# bqZUM_MCU.net
KiCad netlist of a schematic drawn in Altium Designer
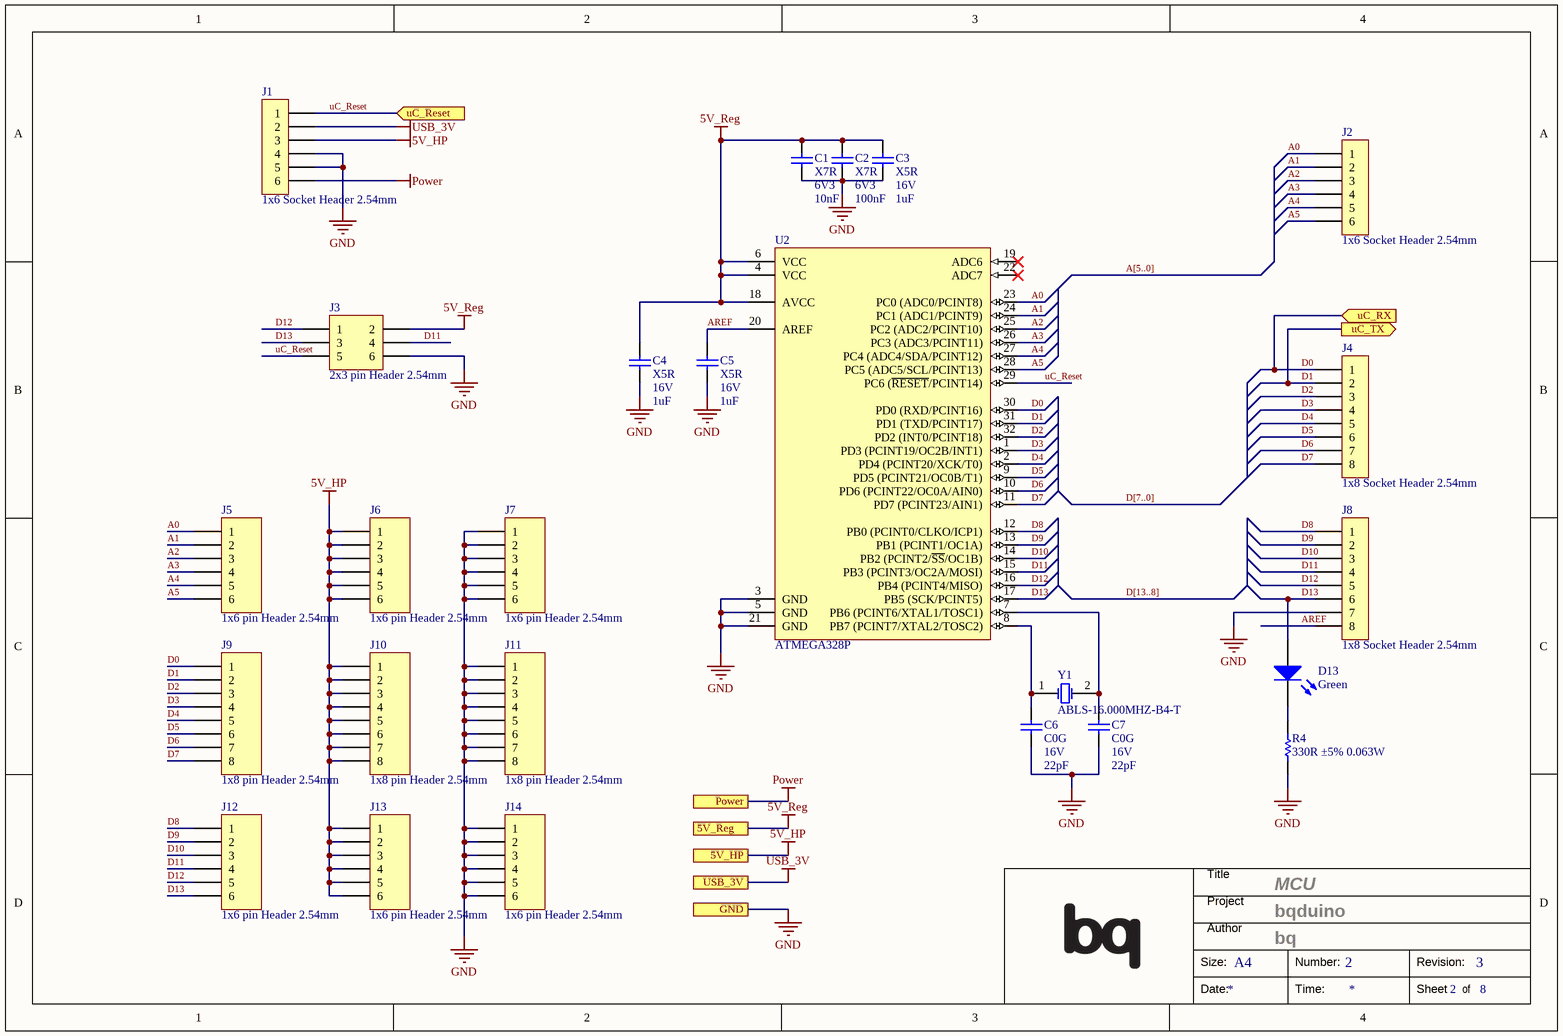
[diagram p0: bqZUM_MCU.SchDoc]

(export (version "E")
  (design (tool "Eeschema 10.0.6"))
  (components
    (comp (ref "C1")
      (value "Capacitor")
      (footprint "C0402")
      (fields
        (field (name "DIELECTRIC") "X7R")
        (field (name "VOLTAGE") "6V3")
        (field (name "CAPACITANCE") "10nF")
        (field (name "PART NUMBER") "C0402_10nF_6V3_±10%")
        (field (name "TOLERANCE") "±10%")
        (field (name "MANUFACTURER") "Kemet")
      )
      (libsource (lib "Pasives_Capacitor_SMD") (part "Capacitor"))
    )
    (comp (ref "C2")
      (value "Capacitor")
      (footprint "C0402")
      (fields
        (field (name "DIELECTRIC") "X7R")
        (field (name "VOLTAGE") "6V3")
        (field (name "CAPACITANCE") "100nF")
        (field (name "PART NUMBER") "C0402_100nF_6V3_±10%")
        (field (name "TOLERANCE") "±10%")
        (field (name "MANUFACTURER") "Kemet")
      )
      (libsource (lib "Pasives_Capacitor_SMD") (part "Capacitor"))
    )
    (comp (ref "C3")
      (value "Capacitor")
      (footprint "C0603")
      (fields
        (field (name "DIELECTRIC") "X5R")
        (field (name "VOLTAGE") "16V")
        (field (name "CAPACITANCE") "1uF")
        (field (name "PART NUMBER") "C0603_1uF_16V_±10%")
        (field (name "TOLERANCE") "±10%")
        (field (name "MANUFACTURER") "Kemet")
      )
      (libsource (lib "Pasives_Capacitor_SMD") (part "Capacitor"))
    )
    (comp (ref "C4")
      (value "Capacitor")
      (footprint "C0603")
      (fields
        (field (name "DIELECTRIC") "X5R")
        (field (name "VOLTAGE") "16V")
        (field (name "CAPACITANCE") "1uF")
        (field (name "PART NUMBER") "C0603_1uF_16V_±10%")
        (field (name "TOLERANCE") "±10%")
        (field (name "MANUFACTURER") "Kemet")
      )
      (libsource (lib "Pasives_Capacitor_SMD") (part "Capacitor"))
    )
    (comp (ref "C5")
      (value "Capacitor")
      (footprint "C0603")
      (fields
        (field (name "DIELECTRIC") "X5R")
        (field (name "VOLTAGE") "16V")
        (field (name "CAPACITANCE") "1uF")
        (field (name "PART NUMBER") "C0603_1uF_16V_±10%")
        (field (name "TOLERANCE") "±10%")
        (field (name "MANUFACTURER") "Kemet")
      )
      (libsource (lib "Pasives_Capacitor_SMD") (part "Capacitor"))
    )
    (comp (ref "C6")
      (value "Capacitor")
      (footprint "C0402")
      (fields
        (field (name "DIELECTRIC") "C0G")
        (field (name "VOLTAGE") "16V")
        (field (name "CAPACITANCE") "22pF")
        (field (name "PART NUMBER") "C0402_22pF_16V_±10%")
        (field (name "TOLERANCE") "±10%")
        (field (name "MANUFACTURER") "Kemet")
      )
      (libsource (lib "Pasives_Capacitor_SMD") (part "Capacitor"))
    )
    (comp (ref "C7")
      (value "Capacitor")
      (footprint "C0402")
      (fields
        (field (name "DIELECTRIC") "C0G")
        (field (name "VOLTAGE") "16V")
        (field (name "CAPACITANCE") "22pF")
        (field (name "PART NUMBER") "C0402_22pF_16V_±10%")
        (field (name "TOLERANCE") "±10%")
        (field (name "MANUFACTURER") "Kemet")
      )
      (libsource (lib "Pasives_Capacitor_SMD") (part "Capacitor"))
    )
    (comp (ref "D13")
      (value "Green")
      (footprint "LED0603")
      (description "Light Emitting Diode")
      (fields (field (name "PART NUMBER") "HSMG-C190") (field (name "MANUFACTURER") "Avago Technologies"))
      (libsource (lib "Optoelectronics") (part "LED"))
    )
    (comp (ref "J1")
      (value "1x6 Socket Header 2.54mm")
      (footprint "1x6 Socket Header THT 2.54mm")
      (description "6 pin Socket Header 2.54mm")
      (fields (field (name "MANUFACTURER") "Samtec") (field (name "PART NUMBER") "CON_SH_THT2.54_6"))
      (libsource (lib "") (part "1x6 Socket Header 2.54mm_1"))
    )
    (comp (ref "J2")
      (value "1x6 Socket Header 2.54mm")
      (footprint "1x6 Socket Header THT 2.54mm")
      (description "6 pin Socket Header 2.54mm")
      (fields (field (name "MANUFACTURER") "Samtec") (field (name "PART NUMBER") "CON_SH_THT2.54_6"))
      (libsource (lib "Conectores_SocketHeader_2.54") (part "1x6 Socket Header 2.54mm"))
    )
    (comp (ref "J3")
      (value "2x3 pin Header 2.54mm")
      (footprint "2x3 Pin Header 2.54")
      (description "6 pin Dual Header 2.54mm")
      (fields (field (name "MANUFACTURER") "Samtec") (field (name "PART NUMBER") "CON_DPH_THT2.54_6"))
      (libsource (lib "Conectores_PinHeader_2.54") (part "2x3 pin Header 2.54mm"))
    )
    (comp (ref "J4")
      (value "1x8 Socket Header 2.54mm")
      (footprint "1x8 Socket Header THT 2.54mm")
      (description "8 pin Socket Header 2.54mm")
      (fields (field (name "MANUFACTURER") "Samtec") (field (name "PART NUMBER") "CON_SH_THT2.54_8"))
      (libsource (lib "Conectores_SocketHeader_2.54") (part "1x8 Socket Header 2.54mm"))
    )
    (comp (ref "J5")
      (value "1x6 pin Header 2.54mm")
      (footprint "1x6 Pin Header 2.54")
      (fields (field (name "MANUFACTURER") "Samtec") (field (name "PART NUMBER") "CON_PH_THT2.54_6 Blue"))
      (libsource (lib "Conectores_PinHeader_2.54") (part "1x6 pin Header 2.54mm"))
    )
    (comp (ref "J6")
      (value "1x6 pin Header 2.54mm")
      (footprint "1x6 Pin Header 2.54")
      (fields (field (name "MANUFACTURER") "Samtec") (field (name "PART NUMBER") "CON_PH_THT2.54_6 Red"))
      (libsource (lib "Conectores_PinHeader_2.54") (part "1x6 pin Header 2.54mm"))
    )
    (comp (ref "J7")
      (value "1x6 pin Header 2.54mm")
      (footprint "1x6 Pin Header 2.54")
      (fields (field (name "MANUFACTURER") "Samtec") (field (name "PART NUMBER") "CON_PH_THT2.54_6"))
      (libsource (lib "Conectores_PinHeader_2.54") (part "1x6 pin Header 2.54mm"))
    )
    (comp (ref "J8")
      (value "1x8 Socket Header 2.54mm")
      (footprint "1x8 Socket Header THT 2.54mm")
      (description "8 pin Socket Header 2.54mm")
      (fields (field (name "MANUFACTURER") "Samtec") (field (name "PART NUMBER") "CON_SH_THT2.54_8"))
      (libsource (lib "Conectores_SocketHeader_2.54") (part "1x8 Socket Header 2.54mm"))
    )
    (comp (ref "J9")
      (value "1x8 pin Header 2.54mm")
      (footprint "1x8 Pin Header 2.54")
      (fields (field (name "MANUFACTURER") "Samtec") (field (name "PART NUMBER") "CON_PH_THT2.54_8 Natural"))
      (libsource (lib "Conectores_PinHeader_2.54") (part "1x8 pin Header 2.54mm"))
    )
    (comp (ref "J10")
      (value "1x8 pin Header 2.54mm")
      (footprint "1x8 Pin Header 2.54")
      (fields (field (name "MANUFACTURER") "Samtec") (field (name "PART NUMBER") "CON_PH_THT2.54_8 Red"))
      (libsource (lib "Conectores_PinHeader_2.54") (part "1x8 pin Header 2.54mm"))
    )
    (comp (ref "J11")
      (value "1x8 pin Header 2.54mm")
      (footprint "1x8 Pin Header 2.54")
      (fields (field (name "MANUFACTURER") "Samtec") (field (name "PART NUMBER") "CON_PH_THT2.54_8"))
      (libsource (lib "Conectores_PinHeader_2.54") (part "1x8 pin Header 2.54mm"))
    )
    (comp (ref "J12")
      (value "1x6 pin Header 2.54mm")
      (footprint "1x6 Pin Header 2.54")
      (fields (field (name "MANUFACTURER") "Samtec") (field (name "PART NUMBER") "CON_PH_THT2.54_6 Natural"))
      (libsource (lib "Conectores_PinHeader_2.54") (part "1x6 pin Header 2.54mm"))
    )
    (comp (ref "J13")
      (value "1x6 pin Header 2.54mm")
      (footprint "1x6 Pin Header 2.54")
      (fields (field (name "MANUFACTURER") "Samtec") (field (name "PART NUMBER") "CON_PH_THT2.54_6 Red"))
      (libsource (lib "Conectores_PinHeader_2.54") (part "1x6 pin Header 2.54mm"))
    )
    (comp (ref "J14")
      (value "1x6 pin Header 2.54mm")
      (footprint "1x6 Pin Header 2.54")
      (fields (field (name "MANUFACTURER") "Samtec") (field (name "PART NUMBER") "CON_PH_THT2.54_6"))
      (libsource (lib "Conectores_PinHeader_2.54") (part "1x6 pin Header 2.54mm"))
    )
    (comp (ref "R4")
      (value "330R ±5% 0.063W")
      (footprint "R0402")
      (description "Resistor")
      (fields (field (name "TOLERANCE") "±5%") (field (name "POWER") "0.063W"))
      (libsource (lib "Pasives_Resistor_SMD") (part "Resistor"))
    )
    (comp (ref "U2")
      (value "ATMEGA328P")
      (footprint "TQFP32")
      (description "8-bit AVR Microcontroller")
      (fields (field (name "MANUFACTURER") "Atmel"))
      (libsource (lib "Processor") (part "ATMEGA328P"))
    )
    (comp (ref "Y1")
      (value "ABLS-16.000MHZ-B4-T")
      (footprint "XTAL 11.4x4.7")
      (description "Crystal")
      (fields (field (name "PART NUMBER") "ABLS 16MHz") (field (name "TOLERANCE") "±30ppm"))
      (libsource (lib "Frequency") (part "Crystal 2 pin"))
    )
  )
  (nets
    (net (code "1") (name "/A0") (class "Default")
      (node (ref "J2") (pin "1") (pinfunction "1_1") (pintype "passive"))
      (node (ref "J5") (pin "1") (pinfunction "1_1") (pintype "passive"))
      (node (ref "U2") (pin "23") (pinfunction "PC0_(ADC0/PCINT8)_23") (pintype "bidirectional"))
    )
    (net (code "2") (name "/A1") (class "Default")
      (node (ref "J2") (pin "2") (pinfunction "2_2") (pintype "passive"))
      (node (ref "J5") (pin "2") (pinfunction "2_2") (pintype "passive"))
      (node (ref "U2") (pin "24") (pinfunction "PC1_(ADC1/PCINT9)_24") (pintype "bidirectional"))
    )
    (net (code "3") (name "/A2") (class "Default")
      (node (ref "J2") (pin "3") (pinfunction "3_3") (pintype "passive"))
      (node (ref "J5") (pin "3") (pinfunction "3_3") (pintype "passive"))
      (node (ref "U2") (pin "25") (pinfunction "PC2_(ADC2/PCINT10)_25") (pintype "bidirectional"))
    )
    (net (code "4") (name "/A3") (class "Default")
      (node (ref "J2") (pin "4") (pinfunction "4_4") (pintype "passive"))
      (node (ref "J5") (pin "4") (pinfunction "4_4") (pintype "passive"))
      (node (ref "U2") (pin "26") (pinfunction "PC3_(ADC3/PCINT11)_26") (pintype "bidirectional"))
    )
    (net (code "5") (name "/A4") (class "Default")
      (node (ref "J2") (pin "5") (pinfunction "5_5") (pintype "passive"))
      (node (ref "J5") (pin "5") (pinfunction "5_5") (pintype "passive"))
      (node (ref "U2") (pin "27") (pinfunction "PC4_(ADC4/SDA/PCINT12)_27") (pintype "bidirectional"))
    )
    (net (code "6") (name "/A5") (class "Default")
      (node (ref "J2") (pin "6") (pinfunction "6_6") (pintype "passive"))
      (node (ref "J5") (pin "6") (pinfunction "6_6") (pintype "passive"))
      (node (ref "U2") (pin "28") (pinfunction "PC5_(ADC5/SCL/PCINT13)_28") (pintype "bidirectional"))
    )
    (net (code "7") (name "/AREF") (class "Default")
      (node (ref "C5") (pin "2") (pinfunction "2_2") (pintype "passive"))
      (node (ref "J8") (pin "8") (pinfunction "8_8") (pintype "passive"))
      (node (ref "U2") (pin "20") (pinfunction "AREF_20") (pintype "passive"))
    )
    (net (code "9") (name "/D0") (class "Default")
      (node (ref "J4") (pin "1") (pinfunction "1_1") (pintype "passive"))
      (node (ref "J9") (pin "1") (pinfunction "1_1") (pintype "passive"))
      (node (ref "U2") (pin "30") (pinfunction "PD0_(RXD/PCINT16)_30") (pintype "bidirectional"))
    )
    (net (code "10") (name "/D1") (class "Default")
      (node (ref "J4") (pin "2") (pinfunction "2_2") (pintype "passive"))
      (node (ref "J9") (pin "2") (pinfunction "2_2") (pintype "passive"))
      (node (ref "U2") (pin "31") (pinfunction "PD1_(TXD/PCINT17)_31") (pintype "bidirectional"))
    )
    (net (code "11") (name "/D2") (class "Default")
      (node (ref "J4") (pin "3") (pinfunction "3_3") (pintype "passive"))
      (node (ref "J9") (pin "3") (pinfunction "3_3") (pintype "passive"))
      (node (ref "U2") (pin "32") (pinfunction "PD2_(INT0/PCINT18)_32") (pintype "bidirectional"))
    )
    (net (code "12") (name "/D3") (class "Default")
      (node (ref "J4") (pin "4") (pinfunction "4_4") (pintype "passive"))
      (node (ref "J9") (pin "4") (pinfunction "4_4") (pintype "passive"))
      (node (ref "U2") (pin "1") (pinfunction "PD3_(PCINT19/OC2B/INT1)_1") (pintype "bidirectional"))
    )
    (net (code "13") (name "/D4") (class "Default")
      (node (ref "J4") (pin "5") (pinfunction "5_5") (pintype "passive"))
      (node (ref "J9") (pin "5") (pinfunction "5_5") (pintype "passive"))
      (node (ref "U2") (pin "2") (pinfunction "PD4_(PCINT20/XCK/T0)_2") (pintype "bidirectional"))
    )
    (net (code "14") (name "/D5") (class "Default")
      (node (ref "J4") (pin "6") (pinfunction "6_6") (pintype "passive"))
      (node (ref "J9") (pin "6") (pinfunction "6_6") (pintype "passive"))
      (node (ref "U2") (pin "9") (pinfunction "PD5_(PCINT21/OC0B/T1)_9") (pintype "bidirectional"))
    )
    (net (code "15") (name "/D6") (class "Default")
      (node (ref "J4") (pin "7") (pinfunction "7_7") (pintype "passive"))
      (node (ref "J9") (pin "7") (pinfunction "7_7") (pintype "passive"))
      (node (ref "U2") (pin "10") (pinfunction "PD6_(PCINT22/OC0A/AIN0)_10") (pintype "bidirectional"))
    )
    (net (code "16") (name "/D7") (class "Default")
      (node (ref "J4") (pin "8") (pinfunction "8_8") (pintype "passive"))
      (node (ref "J9") (pin "8") (pinfunction "8_8") (pintype "passive"))
      (node (ref "U2") (pin "11") (pinfunction "PD7_(PCINT23/AIN1)_11") (pintype "bidirectional"))
    )
    (net (code "17") (name "/D8") (class "Default")
      (node (ref "J12") (pin "1") (pinfunction "1_1") (pintype "passive"))
      (node (ref "J8") (pin "1") (pinfunction "1_1") (pintype "passive"))
      (node (ref "U2") (pin "12") (pinfunction "PB0_(PCINT0/CLKO/ICP1)_12") (pintype "bidirectional"))
    )
    (net (code "18") (name "/D9") (class "Default")
      (node (ref "J12") (pin "2") (pinfunction "2_2") (pintype "passive"))
      (node (ref "J8") (pin "2") (pinfunction "2_2") (pintype "passive"))
      (node (ref "U2") (pin "13") (pinfunction "PB1_(PCINT1/OC1A)_13") (pintype "bidirectional"))
    )
    (net (code "19") (name "/D10") (class "Default")
      (node (ref "J12") (pin "3") (pinfunction "3_3") (pintype "passive"))
      (node (ref "J8") (pin "3") (pinfunction "3_3") (pintype "passive"))
      (node (ref "U2") (pin "14") (pinfunction "PB2_(PCINT2/~{SS}/OC1B)_14") (pintype "bidirectional"))
    )
    (net (code "20") (name "/D11") (class "Default")
      (node (ref "J12") (pin "4") (pinfunction "4_4") (pintype "passive"))
      (node (ref "J3") (pin "4") (pinfunction "4_4") (pintype "passive"))
      (node (ref "J8") (pin "4") (pinfunction "4_4") (pintype "passive"))
      (node (ref "U2") (pin "15") (pinfunction "PB3_(PCINT3/OC2A/MOSI)_15") (pintype "bidirectional"))
    )
    (net (code "21") (name "/D12") (class "Default")
      (node (ref "J12") (pin "5") (pinfunction "5_5") (pintype "passive"))
      (node (ref "J3") (pin "1") (pinfunction "1_1") (pintype "passive"))
      (node (ref "J8") (pin "5") (pinfunction "5_5") (pintype "passive"))
      (node (ref "U2") (pin "16") (pinfunction "PB4_(PCINT4/MISO)_16") (pintype "bidirectional"))
    )
    (net (code "22") (name "/D13") (class "Default")
      (node (ref "D13") (pin "A") (pinfunction "A_A") (pintype "passive"))
      (node (ref "J12") (pin "6") (pinfunction "6_6") (pintype "passive"))
      (node (ref "J3") (pin "3") (pinfunction "3_3") (pintype "passive"))
      (node (ref "J8") (pin "6") (pinfunction "6_6") (pintype "passive"))
      (node (ref "U2") (pin "17") (pinfunction "PB5_(SCK/PCINT5)_17") (pintype "bidirectional"))
    )
    (net (code "25") (name "/uC_Reset") (class "Default")
      (node (ref "J1") (pin "1") (pinfunction "1_1") (pintype "passive"))
      (node (ref "J3") (pin "5") (pinfunction "5_5") (pintype "passive"))
      (node (ref "U2") (pin "29") (pinfunction "PC6_(~{RESET}/PCINT14)_29") (pintype "bidirectional"))
    )
    (net (code "26") (name "5V_HP") (class "Default")
      (node (ref "J1") (pin "3") (pinfunction "3_3") (pintype "passive"))
      (node (ref "J10") (pin "1") (pinfunction "1_1") (pintype "passive"))
      (node (ref "J10") (pin "2") (pinfunction "2_2") (pintype "passive"))
      (node (ref "J10") (pin "3") (pinfunction "3_3") (pintype "passive"))
      (node (ref "J10") (pin "4") (pinfunction "4_4") (pintype "passive"))
      (node (ref "J10") (pin "5") (pinfunction "5_5") (pintype "passive"))
      (node (ref "J10") (pin "6") (pinfunction "6_6") (pintype "passive"))
      (node (ref "J10") (pin "7") (pinfunction "7_7") (pintype "passive"))
      (node (ref "J10") (pin "8") (pinfunction "8_8") (pintype "passive"))
      (node (ref "J13") (pin "1") (pinfunction "1_1") (pintype "passive"))
      (node (ref "J13") (pin "2") (pinfunction "2_2") (pintype "passive"))
      (node (ref "J13") (pin "3") (pinfunction "3_3") (pintype "passive"))
      (node (ref "J13") (pin "4") (pinfunction "4_4") (pintype "passive"))
      (node (ref "J13") (pin "5") (pinfunction "5_5") (pintype "passive"))
      (node (ref "J13") (pin "6") (pinfunction "6_6") (pintype "passive"))
      (node (ref "J6") (pin "1") (pinfunction "1_1") (pintype "passive"))
      (node (ref "J6") (pin "2") (pinfunction "2_2") (pintype "passive"))
      (node (ref "J6") (pin "3") (pinfunction "3_3") (pintype "passive"))
      (node (ref "J6") (pin "4") (pinfunction "4_4") (pintype "passive"))
      (node (ref "J6") (pin "5") (pinfunction "5_5") (pintype "passive"))
      (node (ref "J6") (pin "6") (pinfunction "6_6") (pintype "passive"))
    )
    (net (code "27") (name "5V_Reg") (class "Default")
      (node (ref "C1") (pin "2") (pinfunction "2_2") (pintype "passive"))
      (node (ref "C2") (pin "2") (pinfunction "2_2") (pintype "passive"))
      (node (ref "C3") (pin "2") (pinfunction "2_2") (pintype "passive"))
      (node (ref "C4") (pin "2") (pinfunction "2_2") (pintype "passive"))
      (node (ref "J3") (pin "2") (pinfunction "2_2") (pintype "passive"))
      (node (ref "U2") (pin "18") (pinfunction "AVCC_18") (pintype "power_in"))
      (node (ref "U2") (pin "4") (pinfunction "VCC_4") (pintype "power_in"))
      (node (ref "U2") (pin "6") (pinfunction "VCC_6") (pintype "power_in"))
    )
    (net (code "28") (name "GND") (class "Default")
      (node (ref "C1") (pin "1") (pinfunction "1_1") (pintype "passive"))
      (node (ref "C2") (pin "1") (pinfunction "1_1") (pintype "passive"))
      (node (ref "C3") (pin "1") (pinfunction "1_1") (pintype "passive"))
      (node (ref "C4") (pin "1") (pinfunction "1_1") (pintype "passive"))
      (node (ref "C5") (pin "1") (pinfunction "1_1") (pintype "passive"))
      (node (ref "C6") (pin "1") (pinfunction "1_1") (pintype "passive"))
      (node (ref "C7") (pin "1") (pinfunction "1_1") (pintype "passive"))
      (node (ref "J1") (pin "4") (pinfunction "4_4") (pintype "passive"))
      (node (ref "J1") (pin "5") (pinfunction "5_5") (pintype "passive"))
      (node (ref "J11") (pin "1") (pinfunction "1_1") (pintype "passive"))
      (node (ref "J11") (pin "2") (pinfunction "2_2") (pintype "passive"))
      (node (ref "J11") (pin "3") (pinfunction "3_3") (pintype "passive"))
      (node (ref "J11") (pin "4") (pinfunction "4_4") (pintype "passive"))
      (node (ref "J11") (pin "5") (pinfunction "5_5") (pintype "passive"))
      (node (ref "J11") (pin "6") (pinfunction "6_6") (pintype "passive"))
      (node (ref "J11") (pin "7") (pinfunction "7_7") (pintype "passive"))
      (node (ref "J11") (pin "8") (pinfunction "8_8") (pintype "passive"))
      (node (ref "J14") (pin "1") (pinfunction "1_1") (pintype "passive"))
      (node (ref "J14") (pin "2") (pinfunction "2_2") (pintype "passive"))
      (node (ref "J14") (pin "3") (pinfunction "3_3") (pintype "passive"))
      (node (ref "J14") (pin "4") (pinfunction "4_4") (pintype "passive"))
      (node (ref "J14") (pin "5") (pinfunction "5_5") (pintype "passive"))
      (node (ref "J14") (pin "6") (pinfunction "6_6") (pintype "passive"))
      (node (ref "J3") (pin "6") (pinfunction "6_6") (pintype "passive"))
      (node (ref "J7") (pin "1") (pinfunction "1_1") (pintype "passive"))
      (node (ref "J7") (pin "2") (pinfunction "2_2") (pintype "passive"))
      (node (ref "J7") (pin "3") (pinfunction "3_3") (pintype "passive"))
      (node (ref "J7") (pin "4") (pinfunction "4_4") (pintype "passive"))
      (node (ref "J7") (pin "5") (pinfunction "5_5") (pintype "passive"))
      (node (ref "J7") (pin "6") (pinfunction "6_6") (pintype "passive"))
      (node (ref "J8") (pin "7") (pinfunction "7_7") (pintype "passive"))
      (node (ref "R4") (pin "1") (pinfunction "1_1") (pintype "passive"))
      (node (ref "U2") (pin "21") (pinfunction "GND_21") (pintype "power_in"))
      (node (ref "U2") (pin "3") (pinfunction "GND_3") (pintype "power_in"))
      (node (ref "U2") (pin "5") (pinfunction "GND_5") (pintype "power_in"))
    )
    (net (code "29") (name "Net-(D13-PadK)") (class "Default")
      (node (ref "D13") (pin "K") (pinfunction "K_K") (pintype "passive"))
      (node (ref "R4") (pin "2") (pinfunction "2_2") (pintype "passive"))
    )
    (net (code "30") (name "Net-(U2-PB6_(PCINT6{slash}XTAL1{slash}TOSC1))") (class "Default")
      (node (ref "C7") (pin "2") (pinfunction "2_2") (pintype "passive"))
      (node (ref "U2") (pin "7") (pinfunction "PB6_(PCINT6/XTAL1/TOSC1)_7") (pintype "bidirectional"))
      (node (ref "Y1") (pin "2") (pinfunction "OSC2_2") (pintype "passive"))
    )
    (net (code "31") (name "Net-(U2-PB7_(PCINT7{slash}XTAL2{slash}TOSC2))") (class "Default")
      (node (ref "C6") (pin "2") (pinfunction "2_2") (pintype "passive"))
      (node (ref "U2") (pin "8") (pinfunction "PB7_(PCINT7/XTAL2/TOSC2)_8") (pintype "bidirectional"))
      (node (ref "Y1") (pin "1") (pinfunction "OSC1_1") (pintype "passive"))
    )
    (net (code "32") (name "Power") (class "Default")
      (node (ref "J1") (pin "6") (pinfunction "6_6") (pintype "passive"))
    )
    (net (code "33") (name "USB_3V") (class "Default")
      (node (ref "J1") (pin "2") (pinfunction "2_2") (pintype "passive"))
    )
    (net (code "34") (name "unconnected-(U2-ADC6-Pad19)") (class "Default")
      (node (ref "U2") (pin "19") (pinfunction "ADC6_19") (pintype "input+no_connect"))
    )
    (net (code "35") (name "unconnected-(U2-ADC7-Pad22)") (class "Default")
      (node (ref "U2") (pin "22") (pinfunction "ADC7_22") (pintype "input+no_connect"))
    )
  )
)
